# IRRemoteModule.net
KiCad netlist of a schematic drawn in EAGLE
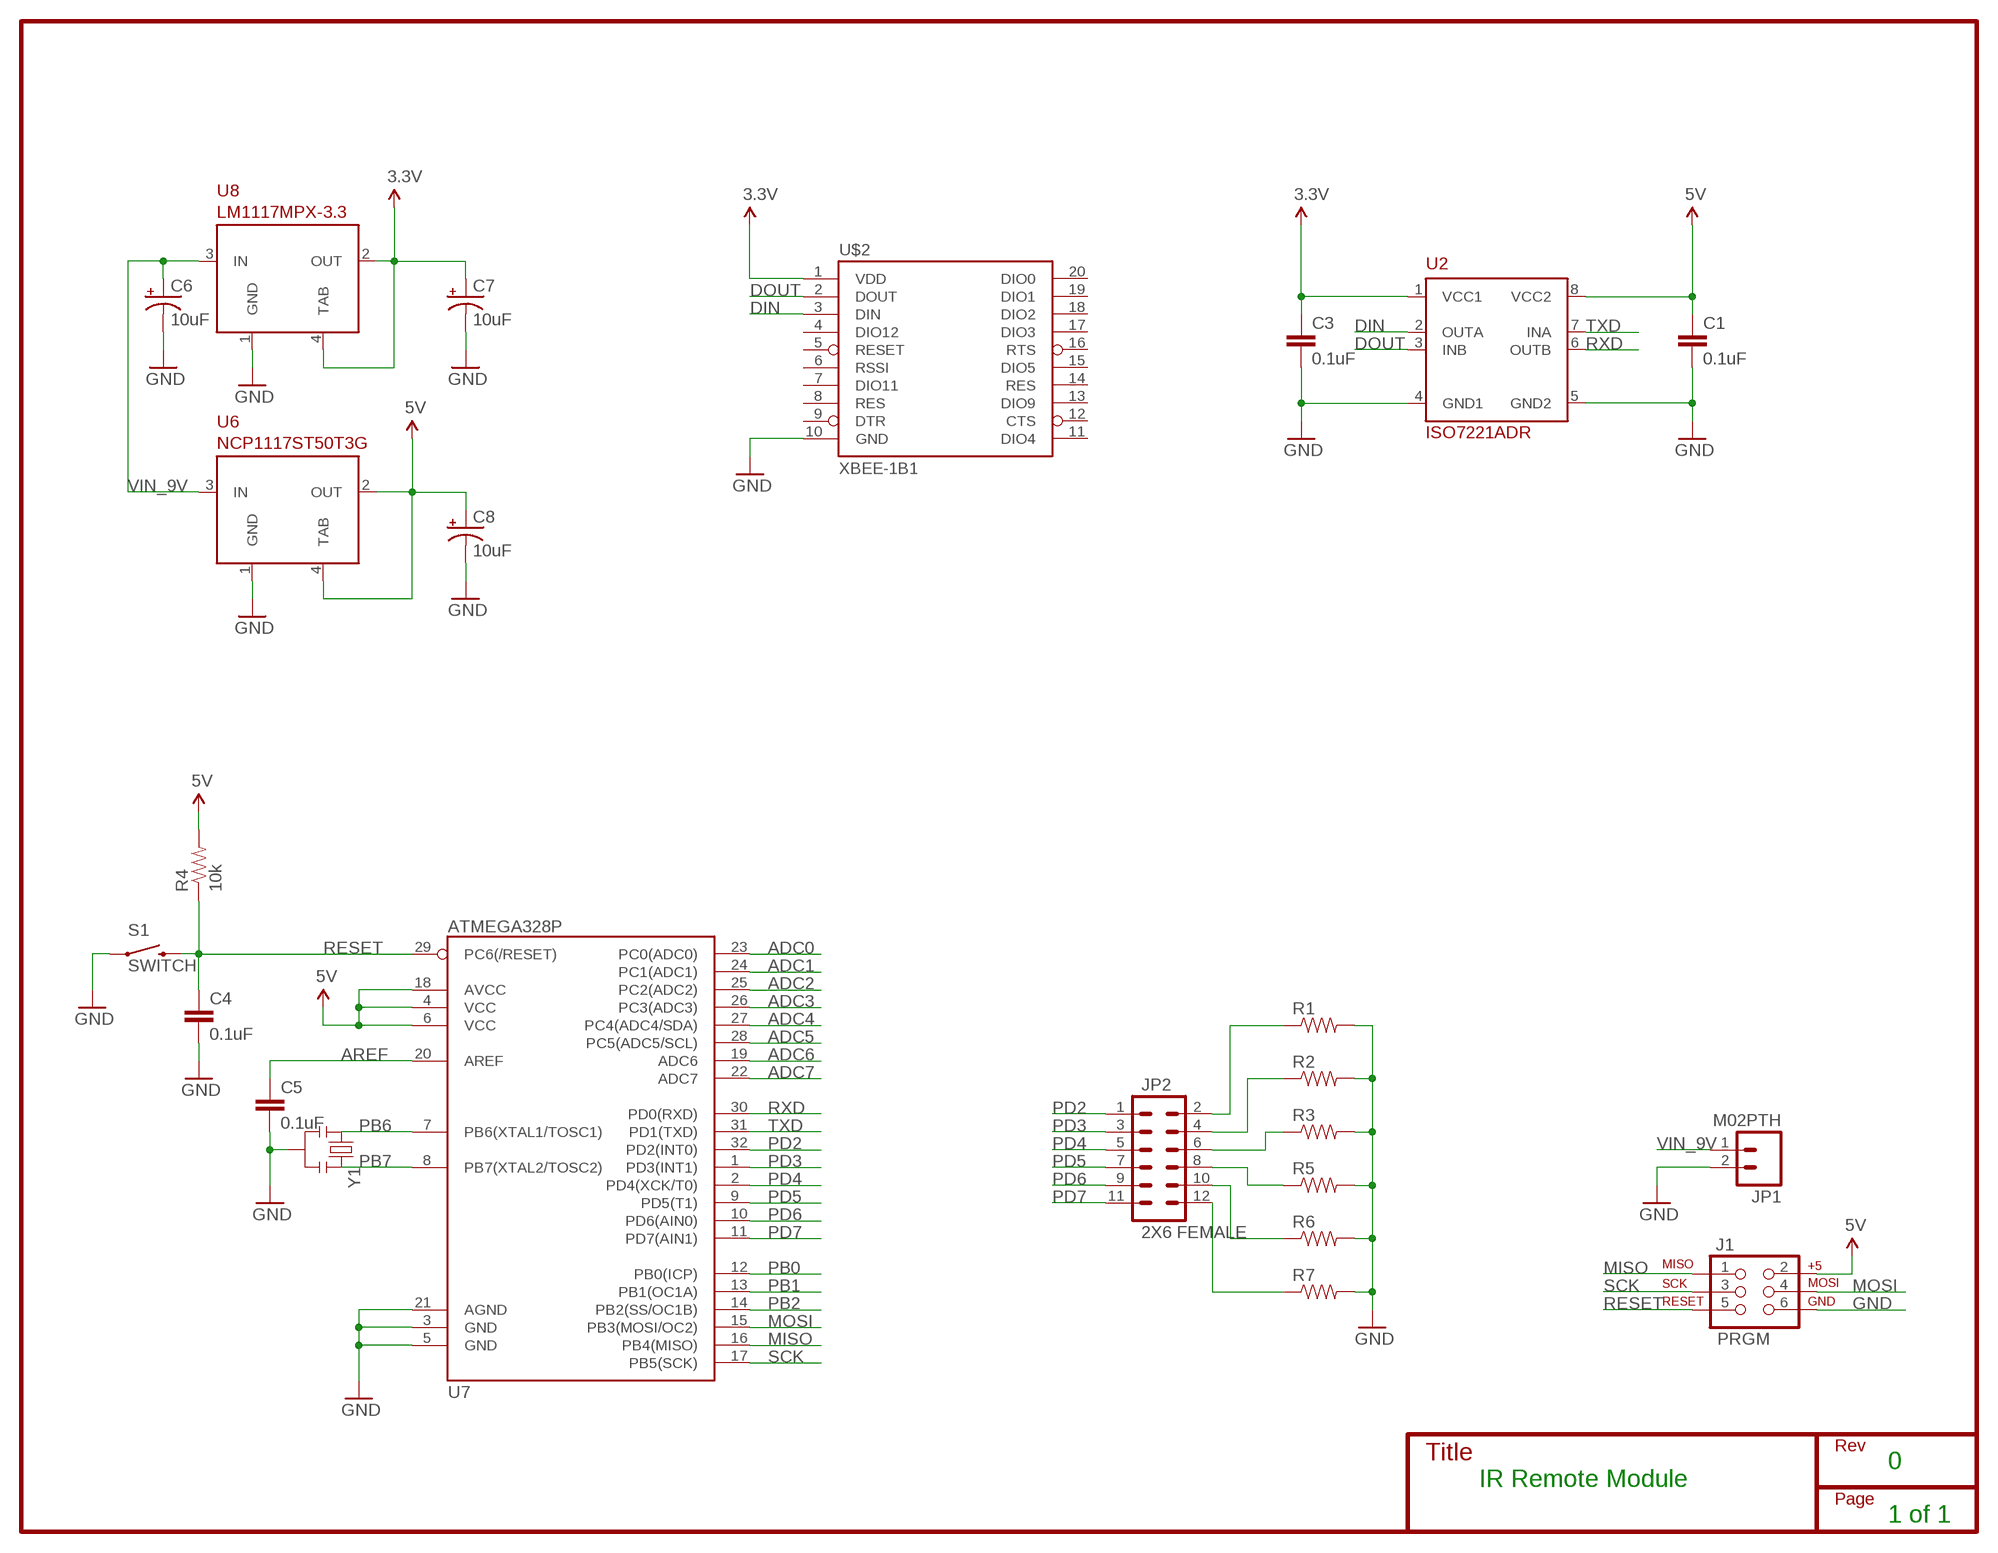
[diagram p0: schematic, sheet 1]

(export (version "E")
  (design (tool "Eeschema 10.0.6"))
  (components
    (comp (ref "C1")
      (value "0.1uF")
      (footprint "eagle-import:0603-CAP")
      (libsource (lib "eagle-import") (part "SparkFun-Passives_CAP0603-CAP"))
    )
    (comp (ref "C3")
      (value "0.1uF")
      (footprint "eagle-import:0603-CAP")
      (libsource (lib "eagle-import") (part "SparkFun-Passives_CAP0603-CAP"))
    )
    (comp (ref "C4")
      (value "0.1uF")
      (footprint "eagle-import:0603-CAP")
      (libsource (lib "eagle-import") (part "CAP0603-CAP"))
    )
    (comp (ref "C5")
      (value "0.1uF")
      (footprint "eagle-import:0603-CAP")
      (libsource (lib "eagle-import") (part "SparkFun-Passives_CAP0603-CAP"))
    )
    (comp (ref "C6")
      (value "10uF")
      (footprint "eagle-import:EIA6032")
      (libsource (lib "eagle-import") (part "CAP_POL6032"))
    )
    (comp (ref "C7")
      (value "10uF")
      (footprint "eagle-import:EIA6032")
      (libsource (lib "eagle-import") (part "CAP_POL6032"))
    )
    (comp (ref "C8")
      (value "10uF")
      (footprint "eagle-import:EIA6032")
      (libsource (lib "eagle-import") (part "CAP_POL6032"))
    )
    (comp (ref "J1")
      (value "PRGM")
      (footprint "eagle-import:2X3")
      (libsource (lib "eagle-import") (part "AVR_SPI_PRG_6PTH"))
    )
    (comp (ref "JP1")
      (value "M02PTH")
      (footprint "eagle-import:1X02")
      (libsource (lib "eagle-import") (part "M02PTH"))
    )
    (comp (ref "JP2")
      (value "2X6 FEMALE")
      (footprint "eagle-import:2X6")
      (libsource (lib "eagle-import") (part "M06X2PTH_FEMALE"))
    )
    (comp (ref "R1")
      (value "RESISTOR0603")
      (footprint "eagle-import:0603-RES")
      (libsource (lib "eagle-import") (part "RESISTOR0603"))
    )
    (comp (ref "R2")
      (value "RESISTOR0603")
      (footprint "eagle-import:0603-RES")
      (libsource (lib "eagle-import") (part "RESISTOR0603"))
    )
    (comp (ref "R3")
      (value "RESISTOR0603")
      (footprint "eagle-import:0603-RES")
      (libsource (lib "eagle-import") (part "RESISTOR0603"))
    )
    (comp (ref "R4")
      (value "10k")
      (footprint "eagle-import:0603-RES")
      (libsource (lib "eagle-import") (part "RESISTOR0603-RES"))
    )
    (comp (ref "R5")
      (value "RESISTOR0603")
      (footprint "eagle-import:0603-RES")
      (libsource (lib "eagle-import") (part "RESISTOR0603"))
    )
    (comp (ref "R6")
      (value "RESISTOR0603")
      (footprint "eagle-import:0603-RES")
      (libsource (lib "eagle-import") (part "RESISTOR0603"))
    )
    (comp (ref "R7")
      (value "RESISTOR0603")
      (footprint "eagle-import:0603-RES")
      (libsource (lib "eagle-import") (part "RESISTOR0603"))
    )
    (comp (ref "S1")
      (value "SWITCH")
      (footprint "eagle-import:TACTILE_SWITCH_SMD")
      (libsource (lib "eagle-import") (part "SWITCH-MOMENTARY-2SMD"))
    )
    (comp (ref "U$2")
      (value "XBEE-1B1")
      (footprint "eagle-import:XBEE-1")
      (libsource (lib "eagle-import") (part "XBEE-1B1"))
    )
    (comp (ref "U2")
      (value "ISO7221ADR")
      (footprint "eagle-import:SO08")
      (fields (field (name "DIGIKEYPART#") "296-21955-1-ND"))
      (libsource (lib "eagle-import") (part "ISO7221ADR"))
    )
    (comp (ref "U6")
      (value "NCP1117ST50T3G")
      (footprint "eagle-import:SOT223")
      (fields (field (name "DIGIKEYPART#") "NCP1117ST50T3GOSCT-ND"))
      (libsource (lib "eagle-import") (part "NCP1117ST50T3G"))
    )
    (comp (ref "U7")
      (value "ATMEGA328P")
      (footprint "eagle-import:TQFP32-08")
      (libsource (lib "eagle-import") (part "ATMEGA328_SMT"))
    )
    (comp (ref "U8")
      (value "LM1117MPX-3.3")
      (footprint "eagle-import:SOT223")
      (fields (field (name "DIGIKEYPART#") "LM1117MPX-3.3/NOPBCT-ND"))
      (libsource (lib "eagle-import") (part "LM1117MPX-3.3"))
    )
    (comp (ref "Y1")
      (value "RESONATORPTH")
      (footprint "eagle-import:RESONATOR-PTH")
      (libsource (lib "eagle-import") (part "RESONATORPTH"))
    )
  )
  (nets
    (net (code "1") (name "/ADC0") (class "Default")
      (node (ref "U7") (pin "23") (pinfunction "PC0(ADC0)_23") (pintype "bidirectional"))
    )
    (net (code "2") (name "/ADC1") (class "Default")
      (node (ref "U7") (pin "24") (pinfunction "PC1(ADC1)_24") (pintype "bidirectional"))
    )
    (net (code "3") (name "/ADC2") (class "Default")
      (node (ref "U7") (pin "25") (pinfunction "PC2(ADC2)_25") (pintype "bidirectional"))
    )
    (net (code "4") (name "/ADC3") (class "Default")
      (node (ref "U7") (pin "26") (pinfunction "PC3(ADC3)_26") (pintype "bidirectional"))
    )
    (net (code "5") (name "/ADC4") (class "Default")
      (node (ref "U7") (pin "27") (pinfunction "PC4(ADC4/SDA)_27") (pintype "bidirectional"))
    )
    (net (code "6") (name "/ADC5") (class "Default")
      (node (ref "U7") (pin "28") (pinfunction "PC5(ADC5/SCL)_28") (pintype "bidirectional"))
    )
    (net (code "7") (name "/ADC6") (class "Default")
      (node (ref "U7") (pin "19") (pinfunction "ADC6_19") (pintype "bidirectional"))
    )
    (net (code "8") (name "/ADC7") (class "Default")
      (node (ref "U7") (pin "22") (pinfunction "ADC7_22") (pintype "bidirectional"))
    )
    (net (code "9") (name "/AREF") (class "Default")
      (node (ref "C5") (pin "1") (pinfunction "1_1") (pintype "passive"))
      (node (ref "U7") (pin "20") (pinfunction "AREF_20") (pintype "bidirectional"))
    )
    (net (code "10") (name "/DIN") (class "Default")
      (node (ref "U$2") (pin "3") (pinfunction "DIN_3") (pintype "input"))
      (node (ref "U2") (pin "2") (pinfunction "OUTA_2") (pintype "bidirectional"))
    )
    (net (code "11") (name "/DOUT") (class "Default")
      (node (ref "U$2") (pin "2") (pinfunction "DOUT_2") (pintype "output"))
      (node (ref "U2") (pin "3") (pinfunction "INB_3") (pintype "bidirectional"))
    )
    (net (code "12") (name "/MISO") (class "Default")
      (node (ref "J1") (pin "1") (pinfunction "1_1") (pintype "passive"))
      (node (ref "U7") (pin "16") (pinfunction "PB4(MISO)_16") (pintype "bidirectional"))
    )
    (net (code "13") (name "/MOSI") (class "Default")
      (node (ref "J1") (pin "4") (pinfunction "4_4") (pintype "passive"))
      (node (ref "U7") (pin "15") (pinfunction "PB3(MOSI/OC2)_15") (pintype "bidirectional"))
    )
    (net (code "14") (name "/PB0") (class "Default")
      (node (ref "U7") (pin "12") (pinfunction "PB0(ICP)_12") (pintype "bidirectional"))
    )
    (net (code "15") (name "/PB1") (class "Default")
      (node (ref "U7") (pin "13") (pinfunction "PB1(OC1A)_13") (pintype "bidirectional"))
    )
    (net (code "16") (name "/PB2") (class "Default")
      (node (ref "U7") (pin "14") (pinfunction "PB2(SS/OC1B)_14") (pintype "bidirectional"))
    )
    (net (code "17") (name "/PB6") (class "Default")
      (node (ref "U7") (pin "7") (pinfunction "PB6(XTAL1/TOSC1)_7") (pintype "bidirectional"))
      (node (ref "Y1") (pin "1") (pinfunction "1_1") (pintype "passive"))
    )
    (net (code "18") (name "/PB7") (class "Default")
      (node (ref "U7") (pin "8") (pinfunction "PB7(XTAL2/TOSC2)_8") (pintype "bidirectional"))
      (node (ref "Y1") (pin "3") (pinfunction "3_3") (pintype "passive"))
    )
    (net (code "19") (name "/PD2") (class "Default")
      (node (ref "JP2") (pin "1") (pinfunction "1_1") (pintype "passive"))
      (node (ref "U7") (pin "32") (pinfunction "PD2(INT0)_32") (pintype "bidirectional"))
    )
    (net (code "20") (name "/PD3") (class "Default")
      (node (ref "JP2") (pin "3") (pinfunction "3_3") (pintype "passive"))
      (node (ref "U7") (pin "1") (pinfunction "PD3(INT1)_1") (pintype "bidirectional"))
    )
    (net (code "21") (name "/PD4") (class "Default")
      (node (ref "JP2") (pin "5") (pinfunction "5_5") (pintype "passive"))
      (node (ref "U7") (pin "2") (pinfunction "PD4(XCK/T0)_2") (pintype "bidirectional"))
    )
    (net (code "22") (name "/PD5") (class "Default")
      (node (ref "JP2") (pin "7") (pinfunction "7_7") (pintype "passive"))
      (node (ref "U7") (pin "9") (pinfunction "PD5(T1)_9") (pintype "bidirectional"))
    )
    (net (code "23") (name "/PD6") (class "Default")
      (node (ref "JP2") (pin "9") (pinfunction "9_9") (pintype "passive"))
      (node (ref "U7") (pin "10") (pinfunction "PD6(AIN0)_10") (pintype "bidirectional"))
    )
    (net (code "24") (name "/PD7") (class "Default")
      (node (ref "JP2") (pin "11") (pinfunction "11_11") (pintype "passive"))
      (node (ref "U7") (pin "11") (pinfunction "PD7(AIN1)_11") (pintype "bidirectional"))
    )
    (net (code "25") (name "/RESET") (class "Default")
      (node (ref "C4") (pin "1") (pinfunction "1_1") (pintype "passive"))
      (node (ref "J1") (pin "5") (pinfunction "5_5") (pintype "passive"))
      (node (ref "R4") (pin "1") (pinfunction "1_1") (pintype "passive"))
      (node (ref "S1") (pin "3") (pinfunction "2_3") (pintype "passive"))
      (node (ref "U7") (pin "29") (pinfunction "PC6(/RESET)_29") (pintype "bidirectional"))
    )
    (net (code "26") (name "/RXD") (class "Default")
      (node (ref "U2") (pin "6") (pinfunction "OUTB_6") (pintype "bidirectional"))
      (node (ref "U7") (pin "30") (pinfunction "PD0(RXD)_30") (pintype "bidirectional"))
    )
    (net (code "27") (name "/SCK") (class "Default")
      (node (ref "J1") (pin "3") (pinfunction "3_3") (pintype "passive"))
      (node (ref "U7") (pin "17") (pinfunction "PB5(SCK)_17") (pintype "bidirectional"))
    )
    (net (code "28") (name "/TXD") (class "Default")
      (node (ref "U2") (pin "7") (pinfunction "INA_7") (pintype "bidirectional"))
      (node (ref "U7") (pin "31") (pinfunction "PD1(TXD)_31") (pintype "bidirectional"))
    )
    (net (code "29") (name "/VIN_9V") (class "Default")
      (node (ref "C6") (pin "P$1") (pinfunction "+_P$1") (pintype "passive"))
      (node (ref "JP1") (pin "1") (pinfunction "1_1") (pintype "passive"))
      (node (ref "U6") (pin "3") (pinfunction "IN_3") (pintype "bidirectional"))
      (node (ref "U8") (pin "3") (pinfunction "IN_3") (pintype "bidirectional"))
    )
    (net (code "30") (name "3.3V") (class "Default")
      (node (ref "C3") (pin "1") (pinfunction "1_1") (pintype "passive"))
      (node (ref "C7") (pin "P$1") (pinfunction "+_P$1") (pintype "passive"))
      (node (ref "U$2") (pin "1") (pinfunction "VDD_1") (pintype "power_in"))
      (node (ref "U2") (pin "1") (pinfunction "VCC1_1") (pintype "bidirectional"))
      (node (ref "U8") (pin "2") (pinfunction "OUT_2") (pintype "bidirectional"))
      (node (ref "U8") (pin "4") (pinfunction "TAB_4") (pintype "bidirectional"))
    )
    (net (code "31") (name "5V") (class "Default")
      (node (ref "C1") (pin "1") (pinfunction "1_1") (pintype "passive"))
      (node (ref "C8") (pin "P$1") (pinfunction "+_P$1") (pintype "passive"))
      (node (ref "J1") (pin "2") (pinfunction "2_2") (pintype "passive"))
      (node (ref "R4") (pin "2") (pinfunction "2_2") (pintype "passive"))
      (node (ref "U2") (pin "8") (pinfunction "VCC2_8") (pintype "bidirectional"))
      (node (ref "U6") (pin "2") (pinfunction "OUT_2") (pintype "bidirectional"))
      (node (ref "U6") (pin "4") (pinfunction "TAB_4") (pintype "bidirectional"))
      (node (ref "U7") (pin "18") (pinfunction "AVCC_18") (pintype "bidirectional"))
      (node (ref "U7") (pin "4") (pinfunction "VCC_4") (pintype "bidirectional"))
      (node (ref "U7") (pin "6") (pinfunction "VCC_6") (pintype "bidirectional"))
    )
    (net (code "32") (name "GND") (class "Default")
      (node (ref "C1") (pin "2") (pinfunction "2_2") (pintype "passive"))
      (node (ref "C3") (pin "2") (pinfunction "2_2") (pintype "passive"))
      (node (ref "C4") (pin "2") (pinfunction "2_2") (pintype "passive"))
      (node (ref "C5") (pin "2") (pinfunction "2_2") (pintype "passive"))
      (node (ref "C6") (pin "P$2") (pinfunction "-_P$2") (pintype "passive"))
      (node (ref "C7") (pin "P$2") (pinfunction "-_P$2") (pintype "passive"))
      (node (ref "C8") (pin "P$2") (pinfunction "-_P$2") (pintype "passive"))
      (node (ref "J1") (pin "6") (pinfunction "6_6") (pintype "passive"))
      (node (ref "JP1") (pin "2") (pinfunction "2_2") (pintype "passive"))
      (node (ref "R1") (pin "2") (pinfunction "2_2") (pintype "passive"))
      (node (ref "R2") (pin "2") (pinfunction "2_2") (pintype "passive"))
      (node (ref "R3") (pin "2") (pinfunction "2_2") (pintype "passive"))
      (node (ref "R5") (pin "2") (pinfunction "2_2") (pintype "passive"))
      (node (ref "R6") (pin "2") (pinfunction "2_2") (pintype "passive"))
      (node (ref "R7") (pin "2") (pinfunction "2_2") (pintype "passive"))
      (node (ref "S1") (pin "1") (pinfunction "1_1") (pintype "passive"))
      (node (ref "U$2") (pin "10") (pinfunction "GND_10") (pintype "power_in"))
      (node (ref "U2") (pin "4") (pinfunction "GND1_4") (pintype "bidirectional"))
      (node (ref "U2") (pin "5") (pinfunction "GND2_5") (pintype "bidirectional"))
      (node (ref "U6") (pin "1") (pinfunction "GND_1") (pintype "bidirectional"))
      (node (ref "U7") (pin "21") (pinfunction "AGND_21") (pintype "bidirectional"))
      (node (ref "U7") (pin "3") (pinfunction "GND_3") (pintype "bidirectional"))
      (node (ref "U7") (pin "5") (pinfunction "GND_5") (pintype "bidirectional"))
      (node (ref "U8") (pin "1") (pinfunction "GND_1") (pintype "bidirectional"))
      (node (ref "Y1") (pin "2") (pinfunction "2_2") (pintype "passive"))
    )
    (net (code "33") (name "Net-(JP2-Pad2)") (class "Default")
      (node (ref "JP2") (pin "2") (pinfunction "2_2") (pintype "passive"))
      (node (ref "R1") (pin "1") (pinfunction "1_1") (pintype "passive"))
    )
    (net (code "34") (name "Net-(JP2-Pad4)") (class "Default")
      (node (ref "JP2") (pin "4") (pinfunction "4_4") (pintype "passive"))
      (node (ref "R2") (pin "1") (pinfunction "1_1") (pintype "passive"))
    )
    (net (code "35") (name "Net-(JP2-Pad6)") (class "Default")
      (node (ref "JP2") (pin "6") (pinfunction "6_6") (pintype "passive"))
      (node (ref "R3") (pin "1") (pinfunction "1_1") (pintype "passive"))
    )
    (net (code "36") (name "Net-(JP2-Pad8)") (class "Default")
      (node (ref "JP2") (pin "8") (pinfunction "8_8") (pintype "passive"))
      (node (ref "R5") (pin "1") (pinfunction "1_1") (pintype "passive"))
    )
    (net (code "37") (name "Net-(JP2-Pad10)") (class "Default")
      (node (ref "JP2") (pin "10") (pinfunction "10_10") (pintype "passive"))
      (node (ref "R6") (pin "1") (pinfunction "1_1") (pintype "passive"))
    )
    (net (code "38") (name "Net-(JP2-Pad12)") (class "Default")
      (node (ref "JP2") (pin "12") (pinfunction "12_12") (pintype "passive"))
      (node (ref "R7") (pin "1") (pinfunction "1_1") (pintype "passive"))
    )
    (net (code "39") (name "unconnected-(U$2-CTS-Pad12)") (class "Default")
      (node (ref "U$2") (pin "12") (pinfunction "CTS_12") (pintype "output"))
    )
    (net (code "40") (name "unconnected-(U$2-DIO0-Pad20)") (class "Default")
      (node (ref "U$2") (pin "20") (pinfunction "DIO0_20") (pintype "bidirectional"))
    )
    (net (code "41") (name "unconnected-(U$2-DIO1-Pad19)") (class "Default")
      (node (ref "U$2") (pin "19") (pinfunction "DIO1_19") (pintype "bidirectional"))
    )
    (net (code "42") (name "unconnected-(U$2-DIO2-Pad18)") (class "Default")
      (node (ref "U$2") (pin "18") (pinfunction "DIO2_18") (pintype "bidirectional"))
    )
    (net (code "43") (name "unconnected-(U$2-DIO3-Pad17)") (class "Default")
      (node (ref "U$2") (pin "17") (pinfunction "DIO3_17") (pintype "bidirectional"))
    )
    (net (code "44") (name "unconnected-(U$2-DIO4-Pad11)") (class "Default")
      (node (ref "U$2") (pin "11") (pinfunction "DIO4_11") (pintype "bidirectional"))
    )
    (net (code "45") (name "unconnected-(U$2-DIO5-Pad15)") (class "Default")
      (node (ref "U$2") (pin "15") (pinfunction "DIO5_15") (pintype "bidirectional"))
    )
    (net (code "46") (name "unconnected-(U$2-DIO9-Pad13)") (class "Default")
      (node (ref "U$2") (pin "13") (pinfunction "DIO9_13") (pintype "bidirectional"))
    )
    (net (code "47") (name "unconnected-(U$2-DIO11-Pad7)") (class "Default")
      (node (ref "U$2") (pin "7") (pinfunction "DIO11_7") (pintype "bidirectional"))
    )
    (net (code "48") (name "unconnected-(U$2-DIO12-Pad4)") (class "Default")
      (node (ref "U$2") (pin "4") (pinfunction "DIO12_4") (pintype "bidirectional"))
    )
    (net (code "49") (name "unconnected-(U$2-DTR-Pad9)") (class "Default")
      (node (ref "U$2") (pin "9") (pinfunction "DTR_9") (pintype "bidirectional"))
    )
    (net (code "50") (name "unconnected-(U$2-RES-Pad8)") (class "Default")
      (node (ref "U$2") (pin "8") (pinfunction "RES_8") (pintype "bidirectional"))
    )
    (net (code "51") (name "unconnected-(U$2-RES-Pad14)") (class "Default")
      (node (ref "U$2") (pin "14") (pinfunction "RES_14") (pintype "bidirectional"))
    )
    (net (code "52") (name "unconnected-(U$2-RESET-Pad5)") (class "Default")
      (node (ref "U$2") (pin "5") (pinfunction "RESET_5") (pintype "input"))
    )
    (net (code "53") (name "unconnected-(U$2-RSSI-Pad6)") (class "Default")
      (node (ref "U$2") (pin "6") (pinfunction "RSSI_6") (pintype "bidirectional"))
    )
    (net (code "54") (name "unconnected-(U$2-RTS-Pad16)") (class "Default")
      (node (ref "U$2") (pin "16") (pinfunction "RTS_16") (pintype "input"))
    )
  )
)
